# projetElecEagle.net
KiCad netlist of a schematic drawn in EAGLE
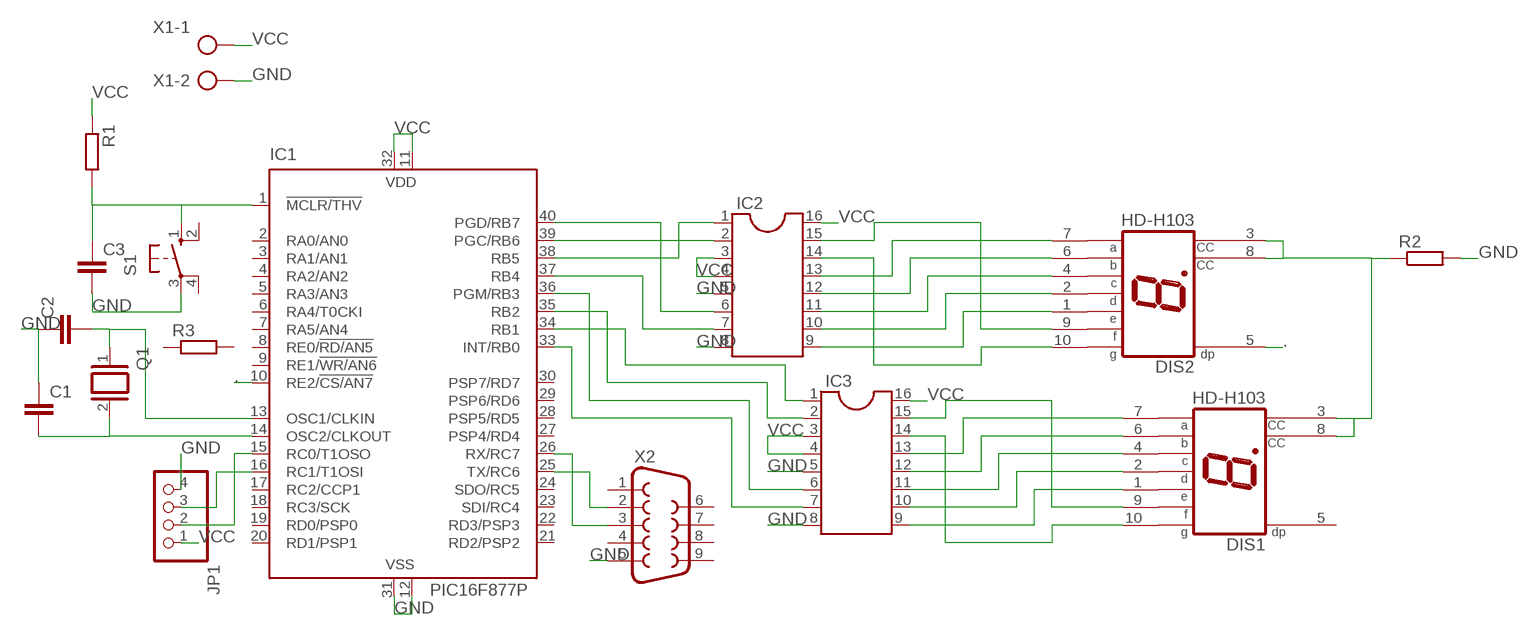
[diagram p0: schematic, sheet 1]

(export (version "E")
  (design (tool "Eeschema 10.0.6"))
  (components
    (comp (ref "C1")
      (value "C-EU025-025X050")
      (footprint "eagle-import:C025-025X050")
      (libsource (lib "eagle-import") (part "C-EU025-025X050"))
    )
    (comp (ref "C2")
      (value "C-EU025-025X050")
      (footprint "eagle-import:C025-025X050")
      (libsource (lib "eagle-import") (part "C-EU025-025X050"))
    )
    (comp (ref "C3")
      (value "C-EU025-025X050")
      (footprint "eagle-import:C025-025X050")
      (libsource (lib "eagle-import") (part "C-EU025-025X050"))
    )
    (comp (ref "DIS1")
      (value "HD-H103")
      (footprint "eagle-import:HDSP-M")
      (libsource (lib "eagle-import") (part "HD-H103"))
    )
    (comp (ref "DIS2")
      (value "HD-H103")
      (footprint "eagle-import:HDSP-M")
      (libsource (lib "eagle-import") (part "HD-H103"))
    )
    (comp (ref "IC1")
      (value "PIC16F877P")
      (footprint "eagle-import:DIL40")
      (fields (field (name "MF") "MICROCHIP") (field (name "MPN") "PIC16F877-04/P"))
      (libsource (lib "eagle-import") (part "PIC16F87P7"))
    )
    (comp (ref "IC2")
      (value "DIL16")
      (footprint "eagle-import:DIL16")
      (libsource (lib "eagle-import") (part "DIL16"))
    )
    (comp (ref "IC3")
      (value "DIL16")
      (footprint "eagle-import:DIL16")
      (libsource (lib "eagle-import") (part "DIL16"))
    )
    (comp (ref "JP1")
      (value "PINHD-1X4")
      (footprint "eagle-import:1X04")
      (libsource (lib "eagle-import") (part "PINHD-1X4"))
    )
    (comp (ref "Q1")
      (value "XTAL/S")
      (footprint "eagle-import:QS")
      (libsource (lib "eagle-import") (part "XTAL/S"))
    )
    (comp (ref "R1")
      (value "R-EU_0207/10")
      (footprint "eagle-import:0207_10")
      (libsource (lib "eagle-import") (part "R-EU_0207/10"))
    )
    (comp (ref "R2")
      (value "R-EU_0207/10")
      (footprint "eagle-import:0207_10")
      (libsource (lib "eagle-import") (part "R-EU_0207/10"))
    )
    (comp (ref "R3")
      (value "R-EU_0207/10")
      (footprint "eagle-import:0207_10")
      (libsource (lib "eagle-import") (part "R-EU_0207/10"))
    )
    (comp (ref "S1")
      (value "10-XX")
      (footprint "eagle-import:B3F-10XX")
      (fields (field (name "MPN") "B3F-1000"))
      (libsource (lib "eagle-import") (part "10-XX"))
    )
    (comp (ref "X1")
      (value "AK300/2")
      (footprint "eagle-import:AK300_2")
      (libsource (lib "eagle-import") (part "AK300/2"))
    )
    (comp (ref "X2")
      (value "F09H")
      (footprint "eagle-import:F09H")
      (libsource (lib "eagle-import") (part "F09H"))
    )
  )
  (nets
    (net (code "1") (name "/.") (class "Default")
      (node (ref "DIS2") (pin "5") (pinfunction "DP_5") (pintype "passive"))
      (node (ref "IC1") (pin "10") (pinfunction "RE2/~{CS/AN7}_10") (pintype "bidirectional"))
    )
    (net (code "2") (name "/GND") (class "Default")
      (node (ref "C1") (pin "1") (pinfunction "1_1") (pintype "passive"))
      (node (ref "C2") (pin "1") (pinfunction "1_1") (pintype "passive"))
      (node (ref "C3") (pin "2") (pinfunction "2_2") (pintype "passive"))
      (node (ref "IC1") (pin "12") (pinfunction "VSS_12") (pintype "power_in"))
      (node (ref "IC1") (pin "31") (pinfunction "VSS_31") (pintype "power_in"))
      (node (ref "IC2") (pin "5") (pinfunction "5_5") (pintype "passive"))
      (node (ref "IC2") (pin "8") (pinfunction "8_8") (pintype "passive"))
      (node (ref "IC3") (pin "5") (pinfunction "5_5") (pintype "passive"))
      (node (ref "IC3") (pin "8") (pinfunction "8_8") (pintype "passive"))
      (node (ref "JP1") (pin "4") (pinfunction "4_4") (pintype "passive"))
      (node (ref "R2") (pin "2") (pinfunction "2_2") (pintype "passive"))
      (node (ref "S1") (pin "3") (pinfunction "P_3") (pintype "passive"))
      (node (ref "X1") (pin "2") (pinfunction "KL_2") (pintype "passive"))
      (node (ref "X2") (pin "5") (pinfunction "5_5") (pintype "passive"))
    )
    (net (code "3") (name "/VCC") (class "Default")
      (node (ref "IC1") (pin "11") (pinfunction "VDD_11") (pintype "power_in"))
      (node (ref "IC1") (pin "32") (pinfunction "VDD_32") (pintype "power_in"))
      (node (ref "IC2") (pin "16") (pinfunction "16_16") (pintype "passive"))
      (node (ref "IC2") (pin "3") (pinfunction "3_3") (pintype "passive"))
      (node (ref "IC2") (pin "4") (pinfunction "4_4") (pintype "passive"))
      (node (ref "IC3") (pin "16") (pinfunction "16_16") (pintype "passive"))
      (node (ref "IC3") (pin "3") (pinfunction "3_3") (pintype "passive"))
      (node (ref "IC3") (pin "4") (pinfunction "4_4") (pintype "passive"))
      (node (ref "JP1") (pin "1") (pinfunction "1_1") (pintype "passive"))
      (node (ref "R1") (pin "1") (pinfunction "1_1") (pintype "passive"))
      (node (ref "X1") (pin "1") (pinfunction "KL_1") (pintype "passive"))
    )
    (net (code "4") (name "Net-(DIS1-A)") (class "Default")
      (node (ref "DIS1") (pin "7") (pinfunction "A_7") (pintype "passive"))
      (node (ref "IC3") (pin "13") (pinfunction "13_13") (pintype "passive"))
    )
    (net (code "5") (name "Net-(DIS1-B)") (class "Default")
      (node (ref "DIS1") (pin "6") (pinfunction "B_6") (pintype "passive"))
      (node (ref "IC3") (pin "12") (pinfunction "12_12") (pintype "passive"))
    )
    (net (code "6") (name "Net-(DIS1-C)") (class "Default")
      (node (ref "DIS1") (pin "4") (pinfunction "C_4") (pintype "passive"))
      (node (ref "IC3") (pin "11") (pinfunction "11_11") (pintype "passive"))
    )
    (net (code "7") (name "Net-(DIS1-CC-Pad3)") (class "Default")
      (node (ref "DIS1") (pin "3") (pinfunction "CC_3") (pintype "passive"))
      (node (ref "DIS1") (pin "8") (pinfunction "CC_8") (pintype "passive"))
      (node (ref "DIS2") (pin "3") (pinfunction "CC_3") (pintype "passive"))
      (node (ref "DIS2") (pin "8") (pinfunction "CC_8") (pintype "passive"))
      (node (ref "R2") (pin "1") (pinfunction "1_1") (pintype "passive"))
    )
    (net (code "8") (name "Net-(DIS1-D)") (class "Default")
      (node (ref "DIS1") (pin "2") (pinfunction "D_2") (pintype "passive"))
      (node (ref "IC3") (pin "10") (pinfunction "10_10") (pintype "passive"))
    )
    (net (code "9") (name "Net-(DIS1-E)") (class "Default")
      (node (ref "DIS1") (pin "1") (pinfunction "E_1") (pintype "passive"))
      (node (ref "IC3") (pin "9") (pinfunction "9_9") (pintype "passive"))
    )
    (net (code "10") (name "Net-(DIS1-F)") (class "Default")
      (node (ref "DIS1") (pin "9") (pinfunction "F_9") (pintype "passive"))
      (node (ref "IC3") (pin "15") (pinfunction "15_15") (pintype "passive"))
    )
    (net (code "11") (name "Net-(DIS1-G)") (class "Default")
      (node (ref "DIS1") (pin "10") (pinfunction "G_10") (pintype "passive"))
      (node (ref "IC3") (pin "14") (pinfunction "14_14") (pintype "passive"))
    )
    (net (code "12") (name "Net-(DIS2-A)") (class "Default")
      (node (ref "DIS2") (pin "7") (pinfunction "A_7") (pintype "passive"))
      (node (ref "IC2") (pin "13") (pinfunction "13_13") (pintype "passive"))
    )
    (net (code "13") (name "Net-(DIS2-B)") (class "Default")
      (node (ref "DIS2") (pin "6") (pinfunction "B_6") (pintype "passive"))
      (node (ref "IC2") (pin "12") (pinfunction "12_12") (pintype "passive"))
    )
    (net (code "14") (name "Net-(DIS2-C)") (class "Default")
      (node (ref "DIS2") (pin "4") (pinfunction "C_4") (pintype "passive"))
      (node (ref "IC2") (pin "11") (pinfunction "11_11") (pintype "passive"))
    )
    (net (code "15") (name "Net-(DIS2-D)") (class "Default")
      (node (ref "DIS2") (pin "2") (pinfunction "D_2") (pintype "passive"))
      (node (ref "IC2") (pin "10") (pinfunction "10_10") (pintype "passive"))
    )
    (net (code "16") (name "Net-(DIS2-E)") (class "Default")
      (node (ref "DIS2") (pin "1") (pinfunction "E_1") (pintype "passive"))
      (node (ref "IC2") (pin "9") (pinfunction "9_9") (pintype "passive"))
    )
    (net (code "17") (name "Net-(DIS2-F)") (class "Default")
      (node (ref "DIS2") (pin "9") (pinfunction "F_9") (pintype "passive"))
      (node (ref "IC2") (pin "15") (pinfunction "15_15") (pintype "passive"))
    )
    (net (code "18") (name "Net-(DIS2-G)") (class "Default")
      (node (ref "DIS2") (pin "10") (pinfunction "G_10") (pintype "passive"))
      (node (ref "IC2") (pin "14") (pinfunction "14_14") (pintype "passive"))
    )
    (net (code "19") (name "Net-(IC1-INT{slash}RB0)") (class "Default")
      (node (ref "IC1") (pin "33") (pinfunction "INT/RB0_33") (pintype "bidirectional"))
      (node (ref "IC3") (pin "7") (pinfunction "7_7") (pintype "passive"))
    )
    (net (code "20") (name "Net-(IC1-OSC1{slash}CLKIN)") (class "Default")
      (node (ref "C2") (pin "2") (pinfunction "2_2") (pintype "passive"))
      (node (ref "IC1") (pin "13") (pinfunction "OSC1/CLKIN_13") (pintype "input"))
      (node (ref "Q1") (pin "1") (pinfunction "1_1") (pintype "passive"))
    )
    (net (code "21") (name "Net-(IC1-OSC2{slash}CLKOUT)") (class "Default")
      (node (ref "C1") (pin "2") (pinfunction "2_2") (pintype "passive"))
      (node (ref "IC1") (pin "14") (pinfunction "OSC2/CLKOUT_14") (pintype "output"))
      (node (ref "Q1") (pin "2") (pinfunction "2_2") (pintype "passive"))
    )
    (net (code "22") (name "Net-(IC1-PGC{slash}RB6)") (class "Default")
      (node (ref "IC1") (pin "39") (pinfunction "PGC/RB6_39") (pintype "bidirectional"))
      (node (ref "IC2") (pin "2") (pinfunction "2_2") (pintype "passive"))
    )
    (net (code "23") (name "Net-(IC1-PGD{slash}RB7)") (class "Default")
      (node (ref "IC1") (pin "40") (pinfunction "PGD/RB7_40") (pintype "bidirectional"))
      (node (ref "IC2") (pin "6") (pinfunction "6_6") (pintype "passive"))
    )
    (net (code "24") (name "Net-(IC1-PGM{slash}RB3)") (class "Default")
      (node (ref "IC1") (pin "36") (pinfunction "PGM/RB3_36") (pintype "bidirectional"))
      (node (ref "IC3") (pin "6") (pinfunction "6_6") (pintype "passive"))
    )
    (net (code "25") (name "Net-(IC1-RB1)") (class "Default")
      (node (ref "IC1") (pin "34") (pinfunction "RB1_34") (pintype "bidirectional"))
      (node (ref "IC3") (pin "1") (pinfunction "1_1") (pintype "passive"))
    )
    (net (code "26") (name "Net-(IC1-RB2)") (class "Default")
      (node (ref "IC1") (pin "35") (pinfunction "RB2_35") (pintype "bidirectional"))
      (node (ref "IC3") (pin "2") (pinfunction "2_2") (pintype "passive"))
    )
    (net (code "27") (name "Net-(IC1-RB4)") (class "Default")
      (node (ref "IC1") (pin "37") (pinfunction "RB4_37") (pintype "bidirectional"))
      (node (ref "IC2") (pin "7") (pinfunction "7_7") (pintype "passive"))
    )
    (net (code "28") (name "Net-(IC1-RB5)") (class "Default")
      (node (ref "IC1") (pin "38") (pinfunction "RB5_38") (pintype "bidirectional"))
      (node (ref "IC2") (pin "1") (pinfunction "1_1") (pintype "passive"))
    )
    (net (code "29") (name "Net-(IC1-RC0{slash}T1OSO)") (class "Default")
      (node (ref "IC1") (pin "15") (pinfunction "RC0/T1OSO_15") (pintype "bidirectional"))
      (node (ref "JP1") (pin "2") (pinfunction "2_2") (pintype "passive"))
    )
    (net (code "30") (name "Net-(IC1-RC1{slash}T1OSI)") (class "Default")
      (node (ref "IC1") (pin "16") (pinfunction "RC1/T1OSI_16") (pintype "bidirectional"))
      (node (ref "JP1") (pin "3") (pinfunction "3_3") (pintype "passive"))
    )
    (net (code "31") (name "Net-(IC1-RX{slash}RC7)") (class "Default")
      (node (ref "IC1") (pin "26") (pinfunction "RX/RC7_26") (pintype "bidirectional"))
      (node (ref "X2") (pin "3") (pinfunction "3_3") (pintype "passive"))
    )
    (net (code "32") (name "Net-(IC1-TX{slash}RC6)") (class "Default")
      (node (ref "IC1") (pin "25") (pinfunction "TX/RC6_25") (pintype "bidirectional"))
      (node (ref "X2") (pin "2") (pinfunction "2_2") (pintype "passive"))
    )
    (net (code "33") (name "Net-(IC1-~{MCLR{slash}THV})") (class "Default")
      (node (ref "C3") (pin "1") (pinfunction "1_1") (pintype "passive"))
      (node (ref "IC1") (pin "1") (pinfunction "~{MCLR/THV}_1") (pintype "input"))
      (node (ref "R1") (pin "2") (pinfunction "2_2") (pintype "passive"))
      (node (ref "S1") (pin "1") (pinfunction "S_1") (pintype "passive"))
    )
    (net (code "34") (name "unconnected-(DIS1-DP-Pad5)") (class "Default")
      (node (ref "DIS1") (pin "5") (pinfunction "DP_5") (pintype "passive"))
    )
    (net (code "35") (name "unconnected-(IC1-PSP4{slash}RD4-Pad27)") (class "Default")
      (node (ref "IC1") (pin "27") (pinfunction "PSP4/RD4_27") (pintype "bidirectional"))
    )
    (net (code "36") (name "unconnected-(IC1-PSP5{slash}RD5-Pad28)") (class "Default")
      (node (ref "IC1") (pin "28") (pinfunction "PSP5/RD5_28") (pintype "bidirectional"))
    )
    (net (code "37") (name "unconnected-(IC1-PSP6{slash}RD6-Pad29)") (class "Default")
      (node (ref "IC1") (pin "29") (pinfunction "PSP6/RD6_29") (pintype "bidirectional"))
    )
    (net (code "38") (name "unconnected-(IC1-PSP7{slash}RD7-Pad30)") (class "Default")
      (node (ref "IC1") (pin "30") (pinfunction "PSP7/RD7_30") (pintype "bidirectional"))
    )
    (net (code "39") (name "unconnected-(IC1-RA0{slash}AN0-Pad2)") (class "Default")
      (node (ref "IC1") (pin "2") (pinfunction "RA0/AN0_2") (pintype "bidirectional"))
    )
    (net (code "40") (name "unconnected-(IC1-RA1{slash}AN1-Pad3)") (class "Default")
      (node (ref "IC1") (pin "3") (pinfunction "RA1/AN1_3") (pintype "bidirectional"))
    )
    (net (code "41") (name "unconnected-(IC1-RA2{slash}AN2-Pad4)") (class "Default")
      (node (ref "IC1") (pin "4") (pinfunction "RA2/AN2_4") (pintype "bidirectional"))
    )
    (net (code "42") (name "unconnected-(IC1-RA3{slash}AN3-Pad5)") (class "Default")
      (node (ref "IC1") (pin "5") (pinfunction "RA3/AN3_5") (pintype "bidirectional"))
    )
    (net (code "43") (name "unconnected-(IC1-RA4{slash}T0CKI-Pad6)") (class "Default")
      (node (ref "IC1") (pin "6") (pinfunction "RA4/T0CKI_6") (pintype "bidirectional"))
    )
    (net (code "44") (name "unconnected-(IC1-RA5{slash}AN4-Pad7)") (class "Default")
      (node (ref "IC1") (pin "7") (pinfunction "RA5/AN4_7") (pintype "bidirectional"))
    )
    (net (code "45") (name "unconnected-(IC1-RC2{slash}CCP1-Pad17)") (class "Default")
      (node (ref "IC1") (pin "17") (pinfunction "RC2/CCP1_17") (pintype "bidirectional"))
    )
    (net (code "46") (name "unconnected-(IC1-RC3{slash}SCK-Pad18)") (class "Default")
      (node (ref "IC1") (pin "18") (pinfunction "RC3/SCK_18") (pintype "bidirectional"))
    )
    (net (code "47") (name "unconnected-(IC1-RD0{slash}PSP0-Pad19)") (class "Default")
      (node (ref "IC1") (pin "19") (pinfunction "RD0/PSP0_19") (pintype "bidirectional"))
    )
    (net (code "48") (name "unconnected-(IC1-RD1{slash}PSP1-Pad20)") (class "Default")
      (node (ref "IC1") (pin "20") (pinfunction "RD1/PSP1_20") (pintype "bidirectional"))
    )
    (net (code "49") (name "unconnected-(IC1-RD2{slash}PSP2-Pad21)") (class "Default")
      (node (ref "IC1") (pin "21") (pinfunction "RD2/PSP2_21") (pintype "bidirectional"))
    )
    (net (code "50") (name "unconnected-(IC1-RD3{slash}PSP3-Pad22)") (class "Default")
      (node (ref "IC1") (pin "22") (pinfunction "RD3/PSP3_22") (pintype "bidirectional"))
    )
    (net (code "51") (name "unconnected-(IC1-RE0{slash}~{RD{slash}AN5}-Pad8)") (class "Default")
      (node (ref "IC1") (pin "8") (pinfunction "RE0/~{RD/AN5}_8") (pintype "bidirectional"))
    )
    (net (code "52") (name "unconnected-(IC1-RE1{slash}~{WR{slash}AN6}-Pad9)") (class "Default")
      (node (ref "IC1") (pin "9") (pinfunction "RE1/~{WR/AN6}_9") (pintype "bidirectional"))
    )
    (net (code "53") (name "unconnected-(IC1-SDI{slash}RC4-Pad23)") (class "Default")
      (node (ref "IC1") (pin "23") (pinfunction "SDI/RC4_23") (pintype "bidirectional"))
    )
    (net (code "54") (name "unconnected-(IC1-SDO{slash}RC5-Pad24)") (class "Default")
      (node (ref "IC1") (pin "24") (pinfunction "SDO/RC5_24") (pintype "bidirectional"))
    )
    (net (code "55") (name "unconnected-(R3-Pad1)") (class "Default")
      (node (ref "R3") (pin "1") (pinfunction "1_1") (pintype "passive"))
    )
    (net (code "56") (name "unconnected-(R3-Pad2)") (class "Default")
      (node (ref "R3") (pin "2") (pinfunction "2_2") (pintype "passive"))
    )
    (net (code "57") (name "unconnected-(S1-P1-Pad4)") (class "Default")
      (node (ref "S1") (pin "4") (pinfunction "P1_4") (pintype "passive"))
    )
    (net (code "58") (name "unconnected-(S1-S1-Pad2)") (class "Default")
      (node (ref "S1") (pin "2") (pinfunction "S1_2") (pintype "passive"))
    )
    (net (code "59") (name "unconnected-(X2-Pad1)") (class "Default")
      (node (ref "X2") (pin "1") (pinfunction "1_1") (pintype "passive"))
    )
    (net (code "60") (name "unconnected-(X2-Pad4)") (class "Default")
      (node (ref "X2") (pin "4") (pinfunction "4_4") (pintype "passive"))
    )
    (net (code "61") (name "unconnected-(X2-Pad6)") (class "Default")
      (node (ref "X2") (pin "6") (pinfunction "6_6") (pintype "passive"))
    )
    (net (code "62") (name "unconnected-(X2-Pad7)") (class "Default")
      (node (ref "X2") (pin "7") (pinfunction "7_7") (pintype "passive"))
    )
    (net (code "63") (name "unconnected-(X2-Pad8)") (class "Default")
      (node (ref "X2") (pin "8") (pinfunction "8_8") (pintype "passive"))
    )
    (net (code "64") (name "unconnected-(X2-Pad9)") (class "Default")
      (node (ref "X2") (pin "9") (pinfunction "9_9") (pintype "passive"))
    )
  )
)
